# main.net
KiCad netlist of a schematic drawn in EAGLE
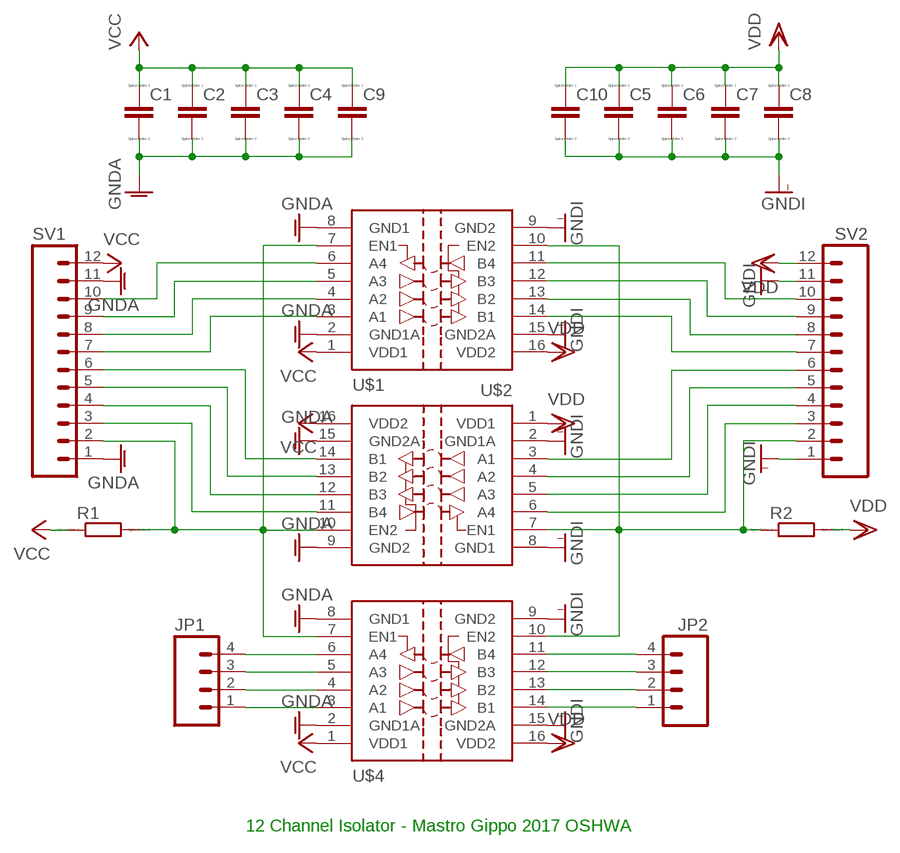
[diagram p0: schematic, sheet 1]

(export (version "E")
  (design (tool "Eeschema 10.0.6"))
  (components
    (comp (ref "C1")
      (value "C-EUC0805K")
      (footprint "eagle-import:C0805K")
      (libsource (lib "eagle-import") (part "C-EUC0805K"))
    )
    (comp (ref "C2")
      (value "C-EUC0805K")
      (footprint "eagle-import:C0805K")
      (libsource (lib "eagle-import") (part "C-EUC0805K"))
    )
    (comp (ref "C3")
      (value "C-EUC0805K")
      (footprint "eagle-import:C0805K")
      (libsource (lib "eagle-import") (part "C-EUC0805K"))
    )
    (comp (ref "C4")
      (value "C-EUC0805K")
      (footprint "eagle-import:C0805K")
      (libsource (lib "eagle-import") (part "C-EUC0805K"))
    )
    (comp (ref "C5")
      (value "C-EUC0805K")
      (footprint "eagle-import:C0805K")
      (libsource (lib "eagle-import") (part "C-EUC0805K"))
    )
    (comp (ref "C6")
      (value "C-EUC0805K")
      (footprint "eagle-import:C0805K")
      (libsource (lib "eagle-import") (part "C-EUC0805K"))
    )
    (comp (ref "C7")
      (value "C-EUC0805K")
      (footprint "eagle-import:C0805K")
      (libsource (lib "eagle-import") (part "C-EUC0805K"))
    )
    (comp (ref "C8")
      (value "C-EUC0805K")
      (footprint "eagle-import:C0805K")
      (libsource (lib "eagle-import") (part "C-EUC0805K"))
    )
    (comp (ref "C9")
      (value "C-EUC0805K")
      (footprint "eagle-import:C0805K")
      (libsource (lib "eagle-import") (part "C-EUC0805K"))
    )
    (comp (ref "C10")
      (value "C-EUC0805K")
      (footprint "eagle-import:C0805K")
      (libsource (lib "eagle-import") (part "C-EUC0805K"))
    )
    (comp (ref "JP1")
      (value "M04LONGPADS")
      (footprint "eagle-import:1X04_LONGPADS")
      (libsource (lib "eagle-import") (part "M04LONGPADS"))
    )
    (comp (ref "JP2")
      (value "M04LONGPADS")
      (footprint "eagle-import:1X04_LONGPADS")
      (libsource (lib "eagle-import") (part "M04LONGPADS"))
    )
    (comp (ref "R1")
      (value "R-EU_M0805")
      (footprint "eagle-import:M0805")
      (libsource (lib "eagle-import") (part "R-EU_M0805"))
    )
    (comp (ref "R2")
      (value "R-EU_M0805")
      (footprint "eagle-import:M0805")
      (libsource (lib "eagle-import") (part "R-EU_M0805"))
    )
    (comp (ref "SV1")
      (value "M12LONGPADS")
      (footprint "eagle-import:1X12_LONGPADS")
      (libsource (lib "eagle-import") (part "M12LONGPADS"))
    )
    (comp (ref "SV2")
      (value "M12LONGPADS")
      (footprint "eagle-import:1X12_LONGPADS")
      (libsource (lib "eagle-import") (part "M12LONGPADS"))
    )
    (comp (ref "U$1")
      (value "SI8441IS")
      (footprint "eagle-import:SO16W")
      (libsource (lib "eagle-import") (part "SI8441IS"))
    )
    (comp (ref "U$2")
      (value "SI8441IS")
      (footprint "eagle-import:SO16W")
      (libsource (lib "eagle-import") (part "SI8441IS"))
    )
    (comp (ref "U$4")
      (value "SI8441IS")
      (footprint "eagle-import:SO16W")
      (libsource (lib "eagle-import") (part "SI8441IS"))
    )
  )
  (nets
    (net (code "1") (name "GNDA") (class "Default")
      (node (ref "C1") (pin "2") (pinfunction "2_2") (pintype "passive"))
      (node (ref "C2") (pin "2") (pinfunction "2_2") (pintype "passive"))
      (node (ref "C3") (pin "2") (pinfunction "2_2") (pintype "passive"))
      (node (ref "C4") (pin "2") (pinfunction "2_2") (pintype "passive"))
      (node (ref "C9") (pin "2") (pinfunction "2_2") (pintype "passive"))
      (node (ref "SV1") (pin "1") (pinfunction "1_1") (pintype "passive"))
      (node (ref "SV1") (pin "11") (pinfunction "11_11") (pintype "passive"))
      (node (ref "U$1") (pin "2") (pinfunction "GND1A_2") (pintype "power_in"))
      (node (ref "U$1") (pin "8") (pinfunction "GND1_8") (pintype "power_in"))
      (node (ref "U$2") (pin "15") (pinfunction "GND2A_15") (pintype "power_in"))
      (node (ref "U$2") (pin "9") (pinfunction "GND2_9") (pintype "power_in"))
      (node (ref "U$4") (pin "2") (pinfunction "GND1A_2") (pintype "power_in"))
      (node (ref "U$4") (pin "8") (pinfunction "GND1_8") (pintype "power_in"))
    )
    (net (code "2") (name "GNDI") (class "Default")
      (node (ref "C10") (pin "2") (pinfunction "2_2") (pintype "passive"))
      (node (ref "C5") (pin "2") (pinfunction "2_2") (pintype "passive"))
      (node (ref "C6") (pin "2") (pinfunction "2_2") (pintype "passive"))
      (node (ref "C7") (pin "2") (pinfunction "2_2") (pintype "passive"))
      (node (ref "C8") (pin "2") (pinfunction "2_2") (pintype "passive"))
      (node (ref "SV2") (pin "1") (pinfunction "1_1") (pintype "passive"))
      (node (ref "SV2") (pin "11") (pinfunction "11_11") (pintype "passive"))
      (node (ref "U$1") (pin "15") (pinfunction "GND2A_15") (pintype "power_in"))
      (node (ref "U$1") (pin "9") (pinfunction "GND2_9") (pintype "power_in"))
      (node (ref "U$2") (pin "2") (pinfunction "GND1A_2") (pintype "power_in"))
      (node (ref "U$2") (pin "8") (pinfunction "GND1_8") (pintype "power_in"))
      (node (ref "U$4") (pin "15") (pinfunction "GND2A_15") (pintype "power_in"))
      (node (ref "U$4") (pin "9") (pinfunction "GND2_9") (pintype "power_in"))
    )
    (net (code "3") (name "Net-(U$1-A1)") (class "Default")
      (node (ref "SV1") (pin "7") (pinfunction "7_7") (pintype "passive"))
      (node (ref "U$1") (pin "3") (pinfunction "A1_3") (pintype "input"))
    )
    (net (code "4") (name "Net-(U$1-A2)") (class "Default")
      (node (ref "SV1") (pin "8") (pinfunction "8_8") (pintype "passive"))
      (node (ref "U$1") (pin "4") (pinfunction "A2_4") (pintype "input"))
    )
    (net (code "5") (name "Net-(U$1-A3)") (class "Default")
      (node (ref "SV1") (pin "9") (pinfunction "9_9") (pintype "passive"))
      (node (ref "U$1") (pin "5") (pinfunction "A3_5") (pintype "input"))
    )
    (net (code "6") (name "Net-(U$1-A4)") (class "Default")
      (node (ref "SV1") (pin "10") (pinfunction "10_10") (pintype "passive"))
      (node (ref "U$1") (pin "6") (pinfunction "A4_6") (pintype "input"))
    )
    (net (code "7") (name "Net-(U$1-B1)") (class "Default")
      (node (ref "SV2") (pin "7") (pinfunction "7_7") (pintype "passive"))
      (node (ref "U$1") (pin "14") (pinfunction "B1_14") (pintype "output"))
    )
    (net (code "8") (name "Net-(U$1-B2)") (class "Default")
      (node (ref "SV2") (pin "8") (pinfunction "8_8") (pintype "passive"))
      (node (ref "U$1") (pin "13") (pinfunction "B2_13") (pintype "output"))
    )
    (net (code "9") (name "Net-(U$1-B3)") (class "Default")
      (node (ref "SV2") (pin "9") (pinfunction "9_9") (pintype "passive"))
      (node (ref "U$1") (pin "12") (pinfunction "B3_12") (pintype "output"))
    )
    (net (code "10") (name "Net-(U$1-B4)") (class "Default")
      (node (ref "SV2") (pin "10") (pinfunction "10_10") (pintype "passive"))
      (node (ref "U$1") (pin "11") (pinfunction "B4_11") (pintype "output"))
    )
    (net (code "11") (name "Net-(U$1-EN1)") (class "Default")
      (node (ref "R1") (pin "2") (pinfunction "2_2") (pintype "passive"))
      (node (ref "SV1") (pin "2") (pinfunction "2_2") (pintype "passive"))
      (node (ref "U$1") (pin "7") (pinfunction "EN1_7") (pintype "input"))
      (node (ref "U$2") (pin "10") (pinfunction "EN2_10") (pintype "input"))
      (node (ref "U$4") (pin "7") (pinfunction "EN1_7") (pintype "input"))
    )
    (net (code "12") (name "Net-(U$1-EN2)") (class "Default")
      (node (ref "R2") (pin "1") (pinfunction "1_1") (pintype "passive"))
      (node (ref "SV2") (pin "2") (pinfunction "2_2") (pintype "passive"))
      (node (ref "U$1") (pin "10") (pinfunction "EN2_10") (pintype "input"))
      (node (ref "U$2") (pin "7") (pinfunction "EN1_7") (pintype "input"))
      (node (ref "U$4") (pin "10") (pinfunction "EN2_10") (pintype "input"))
    )
    (net (code "13") (name "Net-(U$2-A1)") (class "Default")
      (node (ref "SV2") (pin "6") (pinfunction "6_6") (pintype "passive"))
      (node (ref "U$2") (pin "3") (pinfunction "A1_3") (pintype "input"))
    )
    (net (code "14") (name "Net-(U$2-A2)") (class "Default")
      (node (ref "SV2") (pin "5") (pinfunction "5_5") (pintype "passive"))
      (node (ref "U$2") (pin "4") (pinfunction "A2_4") (pintype "input"))
    )
    (net (code "15") (name "Net-(U$2-A3)") (class "Default")
      (node (ref "SV2") (pin "4") (pinfunction "4_4") (pintype "passive"))
      (node (ref "U$2") (pin "5") (pinfunction "A3_5") (pintype "input"))
    )
    (net (code "16") (name "Net-(U$2-A4)") (class "Default")
      (node (ref "SV2") (pin "3") (pinfunction "3_3") (pintype "passive"))
      (node (ref "U$2") (pin "6") (pinfunction "A4_6") (pintype "input"))
    )
    (net (code "17") (name "Net-(U$2-B1)") (class "Default")
      (node (ref "SV1") (pin "6") (pinfunction "6_6") (pintype "passive"))
      (node (ref "U$2") (pin "14") (pinfunction "B1_14") (pintype "output"))
    )
    (net (code "18") (name "Net-(U$2-B2)") (class "Default")
      (node (ref "SV1") (pin "5") (pinfunction "5_5") (pintype "passive"))
      (node (ref "U$2") (pin "13") (pinfunction "B2_13") (pintype "output"))
    )
    (net (code "19") (name "Net-(U$2-B3)") (class "Default")
      (node (ref "SV1") (pin "4") (pinfunction "4_4") (pintype "passive"))
      (node (ref "U$2") (pin "12") (pinfunction "B3_12") (pintype "output"))
    )
    (net (code "20") (name "Net-(U$2-B4)") (class "Default")
      (node (ref "SV1") (pin "3") (pinfunction "3_3") (pintype "passive"))
      (node (ref "U$2") (pin "11") (pinfunction "B4_11") (pintype "output"))
    )
    (net (code "21") (name "Net-(U$4-A1)") (class "Default")
      (node (ref "JP1") (pin "1") (pinfunction "1_1") (pintype "passive"))
      (node (ref "U$4") (pin "3") (pinfunction "A1_3") (pintype "input"))
    )
    (net (code "22") (name "Net-(U$4-A2)") (class "Default")
      (node (ref "JP1") (pin "2") (pinfunction "2_2") (pintype "passive"))
      (node (ref "U$4") (pin "4") (pinfunction "A2_4") (pintype "input"))
    )
    (net (code "23") (name "Net-(U$4-A3)") (class "Default")
      (node (ref "JP1") (pin "3") (pinfunction "3_3") (pintype "passive"))
      (node (ref "U$4") (pin "5") (pinfunction "A3_5") (pintype "input"))
    )
    (net (code "24") (name "Net-(U$4-A4)") (class "Default")
      (node (ref "JP1") (pin "4") (pinfunction "4_4") (pintype "passive"))
      (node (ref "U$4") (pin "6") (pinfunction "A4_6") (pintype "input"))
    )
    (net (code "25") (name "Net-(U$4-B1)") (class "Default")
      (node (ref "JP2") (pin "1") (pinfunction "1_1") (pintype "passive"))
      (node (ref "U$4") (pin "14") (pinfunction "B1_14") (pintype "output"))
    )
    (net (code "26") (name "Net-(U$4-B2)") (class "Default")
      (node (ref "JP2") (pin "2") (pinfunction "2_2") (pintype "passive"))
      (node (ref "U$4") (pin "13") (pinfunction "B2_13") (pintype "output"))
    )
    (net (code "27") (name "Net-(U$4-B3)") (class "Default")
      (node (ref "JP2") (pin "3") (pinfunction "3_3") (pintype "passive"))
      (node (ref "U$4") (pin "12") (pinfunction "B3_12") (pintype "output"))
    )
    (net (code "28") (name "Net-(U$4-B4)") (class "Default")
      (node (ref "JP2") (pin "4") (pinfunction "4_4") (pintype "passive"))
      (node (ref "U$4") (pin "11") (pinfunction "B4_11") (pintype "output"))
    )
    (net (code "29") (name "VCC") (class "Default")
      (node (ref "C1") (pin "1") (pinfunction "1_1") (pintype "passive"))
      (node (ref "C2") (pin "1") (pinfunction "1_1") (pintype "passive"))
      (node (ref "C3") (pin "1") (pinfunction "1_1") (pintype "passive"))
      (node (ref "C4") (pin "1") (pinfunction "1_1") (pintype "passive"))
      (node (ref "C9") (pin "1") (pinfunction "1_1") (pintype "passive"))
      (node (ref "R1") (pin "1") (pinfunction "1_1") (pintype "passive"))
      (node (ref "SV1") (pin "12") (pinfunction "12_12") (pintype "passive"))
      (node (ref "U$1") (pin "1") (pinfunction "VDD1_1") (pintype "power_in"))
      (node (ref "U$2") (pin "16") (pinfunction "VDD2_16") (pintype "power_in"))
      (node (ref "U$4") (pin "1") (pinfunction "VDD1_1") (pintype "power_in"))
    )
    (net (code "30") (name "VDD") (class "Default")
      (node (ref "C10") (pin "1") (pinfunction "1_1") (pintype "passive"))
      (node (ref "C5") (pin "1") (pinfunction "1_1") (pintype "passive"))
      (node (ref "C6") (pin "1") (pinfunction "1_1") (pintype "passive"))
      (node (ref "C7") (pin "1") (pinfunction "1_1") (pintype "passive"))
      (node (ref "C8") (pin "1") (pinfunction "1_1") (pintype "passive"))
      (node (ref "R2") (pin "2") (pinfunction "2_2") (pintype "passive"))
      (node (ref "SV2") (pin "12") (pinfunction "12_12") (pintype "passive"))
      (node (ref "U$1") (pin "16") (pinfunction "VDD2_16") (pintype "power_in"))
      (node (ref "U$2") (pin "1") (pinfunction "VDD1_1") (pintype "power_in"))
      (node (ref "U$4") (pin "16") (pinfunction "VDD2_16") (pintype "power_in"))
    )
  )
)
